# AD9363_Control.net
KiCad netlist of a schematic drawn in Altium Designer
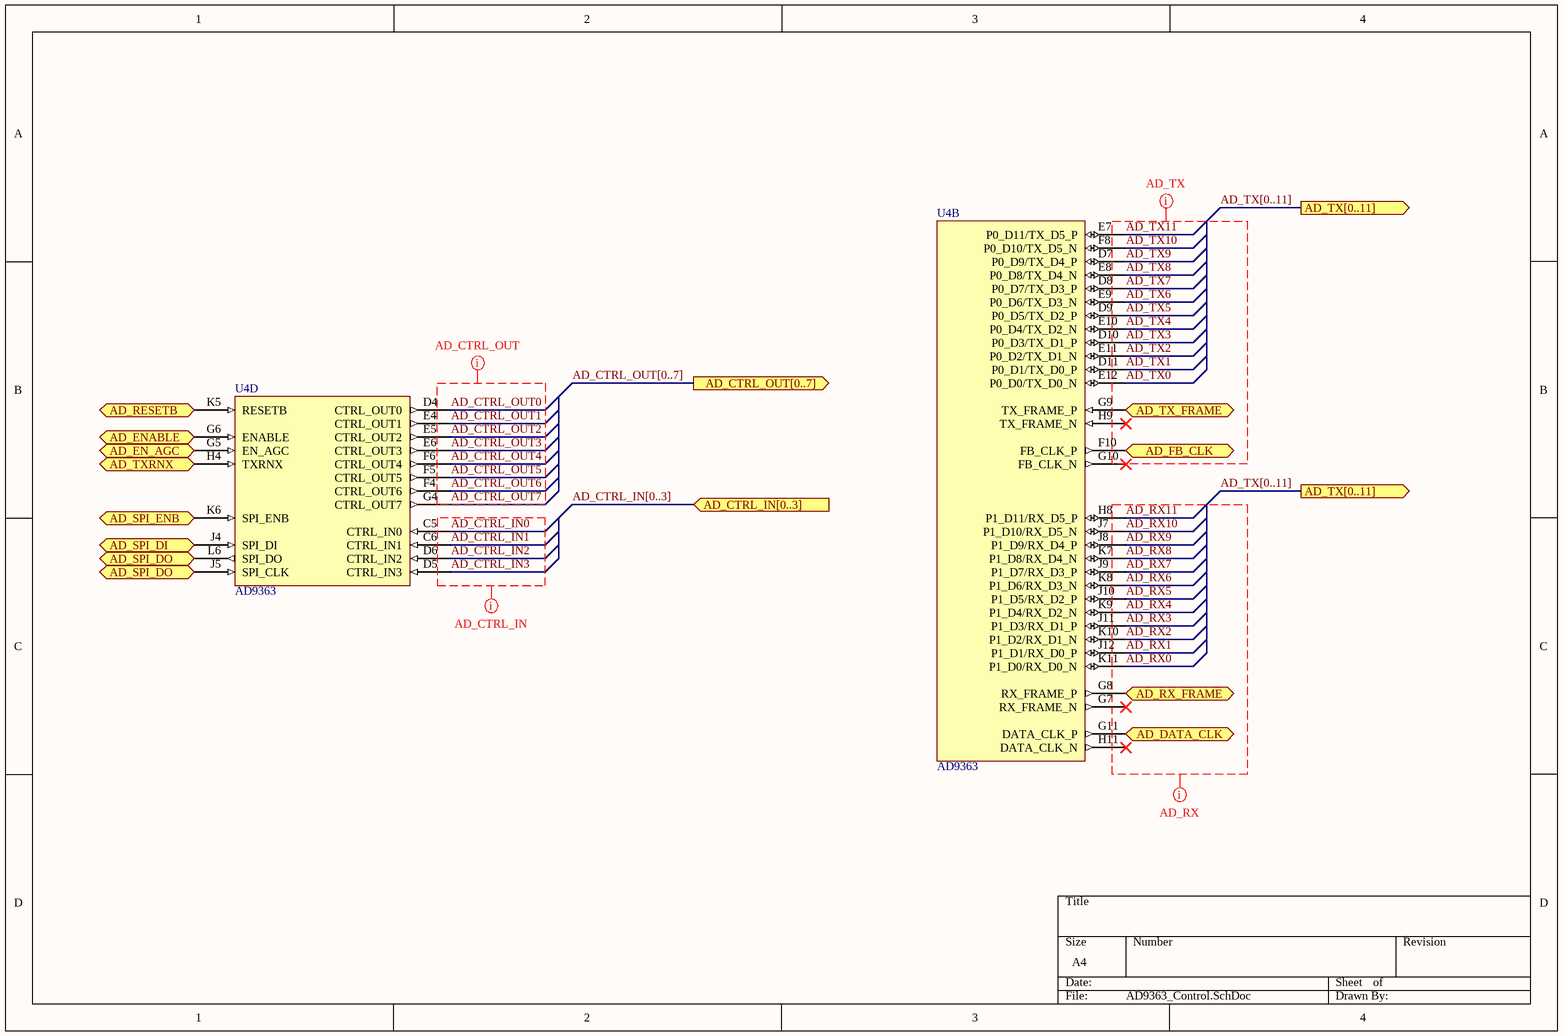
[diagram p0: AD9363_Control.SchDoc]

(export (version "E")
  (design (tool "Eeschema 10.0.6"))
  (components (comp (ref "U4") (value "AD9363") (libsource (lib "WaveRadio") (part "AD9363"))))
  (nets
    (net (code "1") (name "/AD_CTRL_IN0") (class "Default")
      (node (ref "U4") (pin "C5") (pinfunction "CTRL_IN0_C5") (pintype "input"))
    )
    (net (code "2") (name "/AD_CTRL_IN1") (class "Default")
      (node (ref "U4") (pin "C6") (pinfunction "CTRL_IN1_C6") (pintype "input"))
    )
    (net (code "3") (name "/AD_CTRL_IN2") (class "Default")
      (node (ref "U4") (pin "D6") (pinfunction "CTRL_IN2_D6") (pintype "input"))
    )
    (net (code "4") (name "/AD_CTRL_IN3") (class "Default")
      (node (ref "U4") (pin "D5") (pinfunction "CTRL_IN3_D5") (pintype "input"))
    )
    (net (code "6") (name "/AD_CTRL_OUT0") (class "Default")
      (node (ref "U4") (pin "D4") (pinfunction "CTRL_OUT0_D4") (pintype "output"))
    )
    (net (code "7") (name "/AD_CTRL_OUT1") (class "Default")
      (node (ref "U4") (pin "E4") (pinfunction "CTRL_OUT1_E4") (pintype "output"))
    )
    (net (code "8") (name "/AD_CTRL_OUT2") (class "Default")
      (node (ref "U4") (pin "E5") (pinfunction "CTRL_OUT2_E5") (pintype "output"))
    )
    (net (code "9") (name "/AD_CTRL_OUT3") (class "Default")
      (node (ref "U4") (pin "E6") (pinfunction "CTRL_OUT3_E6") (pintype "output"))
    )
    (net (code "10") (name "/AD_CTRL_OUT4") (class "Default")
      (node (ref "U4") (pin "F6") (pinfunction "CTRL_OUT4_F6") (pintype "output"))
    )
    (net (code "11") (name "/AD_CTRL_OUT5") (class "Default")
      (node (ref "U4") (pin "F5") (pinfunction "CTRL_OUT5_F5") (pintype "output"))
    )
    (net (code "12") (name "/AD_CTRL_OUT6") (class "Default")
      (node (ref "U4") (pin "F4") (pinfunction "CTRL_OUT6_F4") (pintype "output"))
    )
    (net (code "13") (name "/AD_CTRL_OUT7") (class "Default")
      (node (ref "U4") (pin "G4") (pinfunction "CTRL_OUT7_G4") (pintype "output"))
    )
    (net (code "15") (name "/AD_DATA_CLK") (class "Default")
      (node (ref "U4") (pin "G11") (pinfunction "DATA_CLK_P_G11") (pintype "output"))
    )
    (net (code "16") (name "/AD_ENABLE") (class "Default")
      (node (ref "U4") (pin "G6") (pinfunction "ENABLE_G6") (pintype "input"))
    )
    (net (code "17") (name "/AD_EN_AGC") (class "Default")
      (node (ref "U4") (pin "G5") (pinfunction "EN_AGC_G5") (pintype "input"))
    )
    (net (code "18") (name "/AD_FB_CLK") (class "Default")
      (node (ref "U4") (pin "F10") (pinfunction "FB_CLK_P_F10") (pintype "output"))
    )
    (net (code "19") (name "/AD_RESETB") (class "Default")
      (node (ref "U4") (pin "K5") (pinfunction "RESETB_K5") (pintype "input"))
    )
    (net (code "20") (name "/AD_RX0") (class "Default")
      (node (ref "U4") (pin "K11") (pinfunction "P1_D0/RX_D0_N_K11") (pintype "bidirectional"))
    )
    (net (code "21") (name "/AD_RX1") (class "Default")
      (node (ref "U4") (pin "J12") (pinfunction "P1_D1/RX_D0_P_J12") (pintype "bidirectional"))
    )
    (net (code "22") (name "/AD_RX2") (class "Default")
      (node (ref "U4") (pin "K10") (pinfunction "P1_D2/RX_D1_N_K10") (pintype "bidirectional"))
    )
    (net (code "23") (name "/AD_RX3") (class "Default")
      (node (ref "U4") (pin "J11") (pinfunction "P1_D3/RX_D1_P_J11") (pintype "bidirectional"))
    )
    (net (code "24") (name "/AD_RX4") (class "Default")
      (node (ref "U4") (pin "K9") (pinfunction "P1_D4/RX_D2_N_K9") (pintype "bidirectional"))
    )
    (net (code "25") (name "/AD_RX5") (class "Default")
      (node (ref "U4") (pin "J10") (pinfunction "P1_D5/RX_D2_P_J10") (pintype "bidirectional"))
    )
    (net (code "26") (name "/AD_RX6") (class "Default")
      (node (ref "U4") (pin "K8") (pinfunction "P1_D6/RX_D3_N_K8") (pintype "bidirectional"))
    )
    (net (code "27") (name "/AD_RX7") (class "Default")
      (node (ref "U4") (pin "J9") (pinfunction "P1_D7/RX_D3_P_J9") (pintype "bidirectional"))
    )
    (net (code "28") (name "/AD_RX8") (class "Default")
      (node (ref "U4") (pin "K7") (pinfunction "P1_D8/RX_D4_N_K7") (pintype "bidirectional"))
    )
    (net (code "29") (name "/AD_RX9") (class "Default")
      (node (ref "U4") (pin "J8") (pinfunction "P1_D9/RX_D4_P_J8") (pintype "bidirectional"))
    )
    (net (code "30") (name "/AD_RX10") (class "Default")
      (node (ref "U4") (pin "J7") (pinfunction "P1_D10/RX_D5_N_J7") (pintype "bidirectional"))
    )
    (net (code "31") (name "/AD_RX11") (class "Default")
      (node (ref "U4") (pin "H8") (pinfunction "P1_D11/RX_D5_P_H8") (pintype "bidirectional"))
    )
    (net (code "32") (name "/AD_RX_FRAME") (class "Default")
      (node (ref "U4") (pin "G8") (pinfunction "RX_FRAME_P_G8") (pintype "output"))
    )
    (net (code "33") (name "/AD_SPI_DI") (class "Default")
      (node (ref "U4") (pin "J4") (pinfunction "SPI_DI_J4") (pintype "input"))
    )
    (net (code "34") (name "/AD_SPI_DO") (class "Default")
      (node (ref "U4") (pin "J5") (pinfunction "SPI_CLK_J5") (pintype "input"))
      (node (ref "U4") (pin "L6") (pinfunction "SPI_DO_L6") (pintype "output"))
    )
    (net (code "35") (name "/AD_SPI_ENB") (class "Default")
      (node (ref "U4") (pin "K6") (pinfunction "SPI_ENB_K6") (pintype "input"))
    )
    (net (code "36") (name "/AD_TX0") (class "Default")
      (node (ref "U4") (pin "E12") (pinfunction "P0_D0/TX_D0_N_E12") (pintype "bidirectional"))
    )
    (net (code "37") (name "/AD_TX1") (class "Default")
      (node (ref "U4") (pin "D11") (pinfunction "P0_D1/TX_D0_P_D11") (pintype "bidirectional"))
    )
    (net (code "38") (name "/AD_TX2") (class "Default")
      (node (ref "U4") (pin "E11") (pinfunction "P0_D2/TX_D1_N_E11") (pintype "bidirectional"))
    )
    (net (code "39") (name "/AD_TX3") (class "Default")
      (node (ref "U4") (pin "D10") (pinfunction "P0_D3/TX_D1_P_D10") (pintype "bidirectional"))
    )
    (net (code "40") (name "/AD_TX4") (class "Default")
      (node (ref "U4") (pin "E10") (pinfunction "P0_D4/TX_D2_N_E10") (pintype "bidirectional"))
    )
    (net (code "41") (name "/AD_TX5") (class "Default")
      (node (ref "U4") (pin "D9") (pinfunction "P0_D5/TX_D2_P_D9") (pintype "bidirectional"))
    )
    (net (code "42") (name "/AD_TX6") (class "Default")
      (node (ref "U4") (pin "E9") (pinfunction "P0_D6/TX_D3_N_E9") (pintype "bidirectional"))
    )
    (net (code "43") (name "/AD_TX7") (class "Default")
      (node (ref "U4") (pin "D8") (pinfunction "P0_D7/TX_D3_P_D8") (pintype "bidirectional"))
    )
    (net (code "44") (name "/AD_TX8") (class "Default")
      (node (ref "U4") (pin "E8") (pinfunction "P0_D8/TX_D4_N_E8") (pintype "bidirectional"))
    )
    (net (code "45") (name "/AD_TX9") (class "Default")
      (node (ref "U4") (pin "D7") (pinfunction "P0_D9/TX_D4_P_D7") (pintype "bidirectional"))
    )
    (net (code "46") (name "/AD_TX10") (class "Default")
      (node (ref "U4") (pin "F8") (pinfunction "P0_D10/TX_D5_N_F8") (pintype "bidirectional"))
    )
    (net (code "47") (name "/AD_TX11") (class "Default")
      (node (ref "U4") (pin "E7") (pinfunction "P0_D11/TX_D5_P_E7") (pintype "bidirectional"))
    )
    (net (code "48") (name "/AD_TXRNX") (class "Default")
      (node (ref "U4") (pin "H4") (pinfunction "TXRNX_H4") (pintype "input"))
    )
    (net (code "50") (name "/AD_TX_FRAME") (class "Default")
      (node (ref "U4") (pin "G9") (pinfunction "TX_FRAME_P_G9") (pintype "input"))
    )
    (net (code "51") (name "unconnected-(U4B-DATA_CLK_N-PadH11)") (class "Default")
      (node (ref "U4") (pin "H11") (pinfunction "DATA_CLK_N_H11") (pintype "output+no_connect"))
    )
    (net (code "52") (name "unconnected-(U4B-FB_CLK_N-PadG10)") (class "Default")
      (node (ref "U4") (pin "G10") (pinfunction "FB_CLK_N_G10") (pintype "output+no_connect"))
    )
    (net (code "53") (name "unconnected-(U4B-RX_FRAME_N-PadG7)") (class "Default")
      (node (ref "U4") (pin "G7") (pinfunction "RX_FRAME_N_G7") (pintype "output+no_connect"))
    )
    (net (code "54") (name "unconnected-(U4B-TX_FRAME_N-PadH9)") (class "Default")
      (node (ref "U4") (pin "H9") (pinfunction "TX_FRAME_N_H9") (pintype "input+no_connect"))
    )
  )
)
